# blinky_board.net
KiCad netlist of a schematic drawn in EAGLE
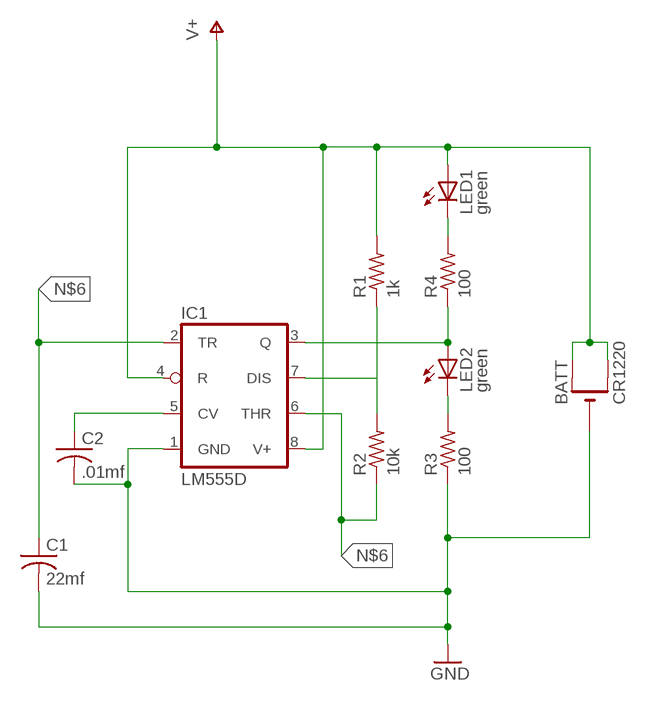
[diagram p0: schematic, sheet 1]

(export (version "E")
  (design (tool "Eeschema 10.0.6"))
  (components
    (comp (ref "BATT")
      (value "CR1220")
      (footprint "eagle-import:CR1220-SMD")
      (fields (field (name "MF") "KEYSTONE") (field (name "MPN") "3000"))
      (libsource (lib "eagle-import") (part "CR1220SMT"))
    )
    (comp (ref "C1")
      (value "22mf")
      (footprint "eagle-import:C0805K")
      (fields (field (name "MF") "TE CONNECTIVITY / CGS") (field (name "MPN") "HBA22MFZRE"))
      (libsource (lib "eagle-import") (part "C-USC0805K"))
    )
    (comp (ref "C2")
      (value ".01mf")
      (footprint "eagle-import:C0805K")
      (fields (field (name "MF") "LITTELFUSE") (field (name "MPN") "60R185XF"))
      (libsource (lib "eagle-import") (part "C-USC0805K"))
    )
    (comp (ref "IC1")
      (value "LM555D")
      (footprint "eagle-import:SO08")
      (fields (field (name "MF") "TEXAS INSTRUMENTS") (field (name "MPN") "LM555CMX/NOPB."))
      (libsource (lib "eagle-import") (part "555DLM"))
    )
    (comp (ref "LED1")
      (value "green")
      (footprint "eagle-import:CHIPLED_0805")
      (fields (field (name "MF") "KINGBRIGHT") (field (name "MPN") "KPHCM-2012CGCK"))
      (libsource (lib "eagle-import") (part "LEDCHIPLED_0805"))
    )
    (comp (ref "LED2")
      (value "green")
      (footprint "eagle-import:CHIPLED_0805")
      (fields (field (name "MF") "KINGBRIGHT") (field (name "MPN") "KPHCM-2012CGCK"))
      (libsource (lib "eagle-import") (part "LEDCHIPLED_0805"))
    )
    (comp (ref "R1")
      (value "1k")
      (footprint "eagle-import:R0805")
      (fields (field (name "MF") "VISHAY") (field (name "MPN") "CRCW06031K00FKEA"))
      (libsource (lib "eagle-import") (part "R-US_R0805"))
    )
    (comp (ref "R2")
      (value "10k")
      (footprint "eagle-import:R0805")
      (fields (field (name "MF") "WELWYN") (field (name "MPN") "MFR4-10KFI"))
      (libsource (lib "eagle-import") (part "R-US_R0805"))
    )
    (comp (ref "R3")
      (value "100")
      (footprint "eagle-import:R0805")
      (fields (field (name "MF") "YAGEO") (field (name "MPN") "RC0402JR-13100RL"))
      (libsource (lib "eagle-import") (part "R-US_R0805"))
    )
    (comp (ref "R4")
      (value "100")
      (footprint "eagle-import:R0805")
      (fields (field (name "MF") "YAGEO") (field (name "MPN") "RC0402JR-13100RL"))
      (libsource (lib "eagle-import") (part "R-US_R0805"))
    )
  )
  (nets
    (net (code "1") (name "GND") (class "Default")
      (node (ref "BATT") (pin "-") (pinfunction "-_-") (pintype "passive"))
      (node (ref "C1") (pin "2") (pinfunction "2_2") (pintype "passive"))
      (node (ref "C2") (pin "2") (pinfunction "2_2") (pintype "passive"))
      (node (ref "IC1") (pin "1") (pinfunction "GND_1") (pintype "power_in"))
      (node (ref "R3") (pin "1") (pinfunction "1_1") (pintype "passive"))
    )
    (net (code "2") (name "N$6") (class "Default")
      (node (ref "C1") (pin "1") (pinfunction "1_1") (pintype "passive"))
      (node (ref "IC1") (pin "2") (pinfunction "TR_2") (pintype "input"))
      (node (ref "IC1") (pin "6") (pinfunction "THR_6") (pintype "input"))
      (node (ref "R2") (pin "1") (pinfunction "1_1") (pintype "passive"))
    )
    (net (code "3") (name "Net-(IC1-CV)") (class "Default")
      (node (ref "C2") (pin "1") (pinfunction "1_1") (pintype "passive"))
      (node (ref "IC1") (pin "5") (pinfunction "CV_5") (pintype "input"))
    )
    (net (code "4") (name "Net-(IC1-DIS)") (class "Default")
      (node (ref "IC1") (pin "7") (pinfunction "DIS_7") (pintype "input"))
      (node (ref "R1") (pin "1") (pinfunction "1_1") (pintype "passive"))
      (node (ref "R2") (pin "2") (pinfunction "2_2") (pintype "passive"))
    )
    (net (code "5") (name "Net-(IC1-Q)") (class "Default")
      (node (ref "IC1") (pin "3") (pinfunction "Q_3") (pintype "output"))
      (node (ref "LED2") (pin "A") (pinfunction "A_A") (pintype "passive"))
      (node (ref "R4") (pin "1") (pinfunction "1_1") (pintype "passive"))
    )
    (net (code "6") (name "Net-(LED1-PadC)") (class "Default")
      (node (ref "LED1") (pin "C") (pinfunction "C_C") (pintype "passive"))
      (node (ref "R4") (pin "2") (pinfunction "2_2") (pintype "passive"))
    )
    (net (code "7") (name "Net-(LED2-PadC)") (class "Default")
      (node (ref "LED2") (pin "C") (pinfunction "C_C") (pintype "passive"))
      (node (ref "R3") (pin "2") (pinfunction "2_2") (pintype "passive"))
    )
    (net (code "8") (name "V+") (class "Default")
      (node (ref "BATT") (pin "+$1") (pinfunction "+_+$1") (pintype "passive"))
      (node (ref "BATT") (pin "+$2") (pinfunction "+1_+$2") (pintype "passive"))
      (node (ref "IC1") (pin "4") (pinfunction "R_4") (pintype "input"))
      (node (ref "IC1") (pin "8") (pinfunction "V+_8") (pintype "power_in"))
      (node (ref "LED1") (pin "A") (pinfunction "A_A") (pintype "passive"))
      (node (ref "R1") (pin "2") (pinfunction "2_2") (pintype "passive"))
    )
  )
)
